# Enclosure_100x68_AMux-M.net
KiCad netlist of a schematic drawn in EAGLE
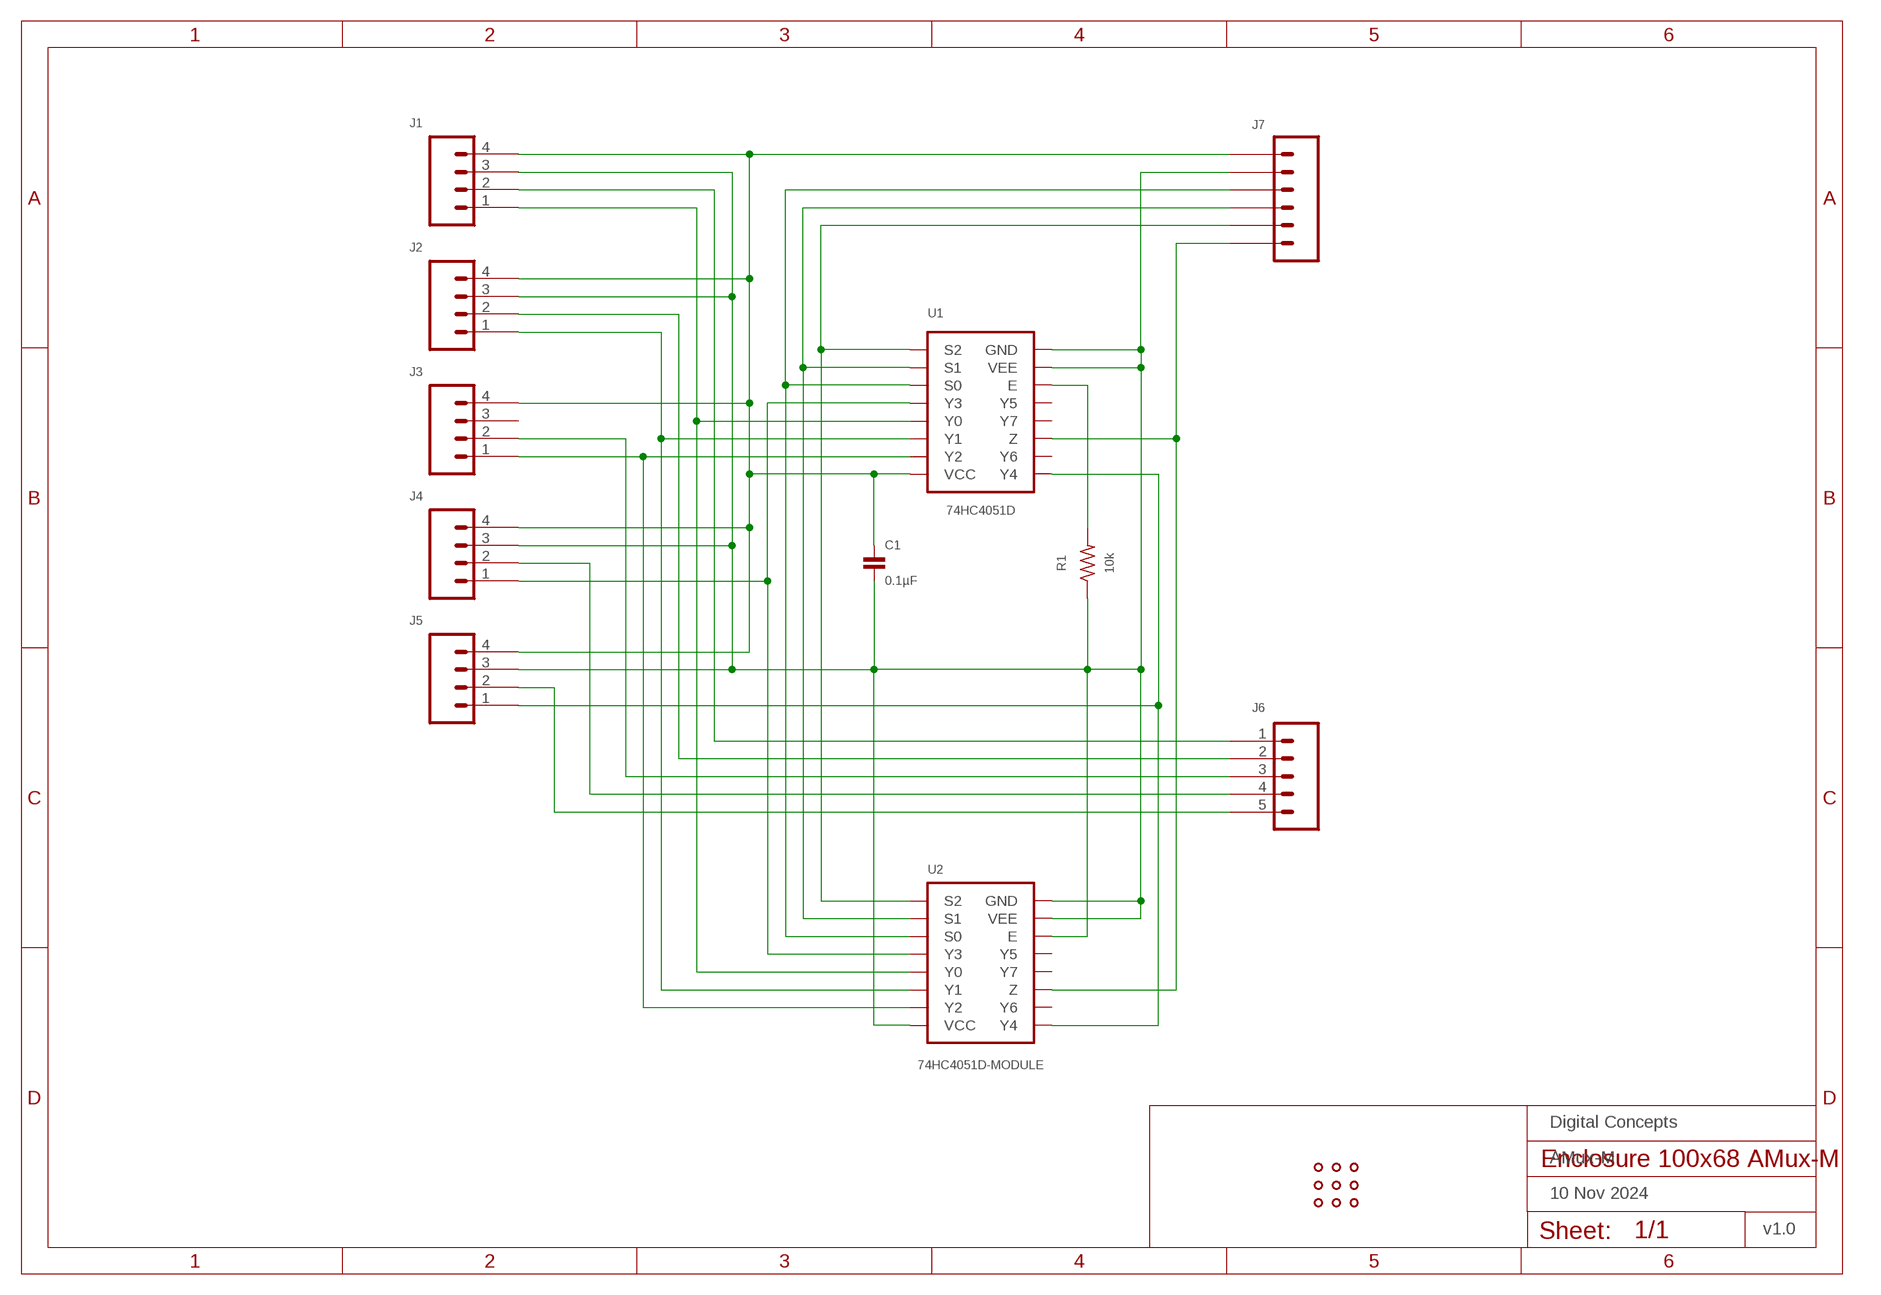
[diagram p0: schematic, sheet 1]

(export (version "E")
  (design (tool "Eeschema 10.0.6"))
  (components
    (comp (ref "C1")
      (value "0.1µF")
      (footprint "eagle-import:C0805")
      (libsource (lib "eagle-import") (part "CAPACITOR-0805"))
    )
    (comp (ref "J1")
      (value "HEADER-1X4-GENERIC")
      (footprint "eagle-import:CONN_04-GENERIC")
      (libsource (lib "eagle-import") (part "HEADER-1X4-GENERIC"))
    )
    (comp (ref "J2")
      (value "HEADER-1X4-GENERIC")
      (footprint "eagle-import:CONN_04-GENERIC")
      (libsource (lib "eagle-import") (part "HEADER-1X4-GENERIC"))
    )
    (comp (ref "J3")
      (value "HEADER-1X4-GENERIC")
      (footprint "eagle-import:CONN_04-GENERIC")
      (libsource (lib "eagle-import") (part "HEADER-1X4-GENERIC"))
    )
    (comp (ref "J4")
      (value "HEADER-1X4-GENERIC")
      (footprint "eagle-import:CONN_04-GENERIC")
      (libsource (lib "eagle-import") (part "HEADER-1X4-GENERIC"))
    )
    (comp (ref "J5")
      (value "HEADER-1X4-GENERIC")
      (footprint "eagle-import:CONN_04-GENERIC")
      (libsource (lib "eagle-import") (part "HEADER-1X4-GENERIC"))
    )
    (comp (ref "J6")
      (value "JST-PH2.0-5-HORIZONTAL")
      (footprint "eagle-import:JST-PH2.0-5-HORIZONTAL")
      (libsource (lib "eagle-import") (part "JST-PH2.0-5-HORIZONTAL"))
    )
    (comp (ref "J7")
      (value "JST-PH2.0-6-HORIZONTAL")
      (footprint "eagle-import:JST-PH2.0-6-HORIZONTAL")
      (libsource (lib "eagle-import") (part "JST-PH2.0-6-HORIZONTAL"))
    )
    (comp (ref "R1")
      (value "10k")
      (footprint "eagle-import:R0805")
      (libsource (lib "eagle-import") (part "RESISTORR0805"))
    )
    (comp (ref "U$1")
      (value "PROTO-34X22-AMUX")
      (footprint "eagle-import:PROTO-34X22-AMUX")
      (libsource (lib "eagle-import") (part "PROTO-34X22-AMUX"))
    )
    (comp (ref "U1")
      (value "74HC4051D")
      (footprint "eagle-import:SOP16")
      (libsource (lib "eagle-import") (part "74HC4051D"))
    )
    (comp (ref "U2")
      (value "74HC4051D-MODULE")
      (footprint "eagle-import:74HC4051D-MODULE")
      (libsource (lib "eagle-import") (part "74HC4051D-MODULE"))
    )
  )
  (nets
    (net (code "1") (name "Net-(J1-Pad2)") (class "Default")
      (node (ref "J1") (pin "2") (pinfunction "2_2") (pintype "passive"))
      (node (ref "J6") (pin "1") (pinfunction "1_1") (pintype "passive"))
    )
    (net (code "2") (name "Net-(J2-Pad2)") (class "Default")
      (node (ref "J2") (pin "2") (pinfunction "2_2") (pintype "passive"))
      (node (ref "J6") (pin "2") (pinfunction "2_2") (pintype "passive"))
    )
    (net (code "3") (name "Net-(J3-Pad2)") (class "Default")
      (node (ref "J3") (pin "2") (pinfunction "2_2") (pintype "passive"))
      (node (ref "J6") (pin "3") (pinfunction "3_3") (pintype "passive"))
    )
    (net (code "4") (name "Net-(J4-Pad2)") (class "Default")
      (node (ref "J4") (pin "2") (pinfunction "2_2") (pintype "passive"))
      (node (ref "J6") (pin "4") (pinfunction "4_4") (pintype "passive"))
    )
    (net (code "5") (name "Net-(J5-Pad2)") (class "Default")
      (node (ref "J5") (pin "2") (pinfunction "2_2") (pintype "passive"))
      (node (ref "J6") (pin "5") (pinfunction "5_5") (pintype "passive"))
    )
    (net (code "6") (name "Net-(U1-E)") (class "Default")
      (node (ref "R1") (pin "2") (pinfunction "2_2") (pintype "passive"))
      (node (ref "U1") (pin "6") (pinfunction "E_6") (pintype "bidirectional"))
    )
    (net (code "7") (name "Net-(U1-GND)") (class "Default")
      (node (ref "C1") (pin "2") (pinfunction "2_2") (pintype "passive"))
      (node (ref "J1") (pin "3") (pinfunction "3_3") (pintype "passive"))
      (node (ref "J2") (pin "3") (pinfunction "3_3") (pintype "passive"))
      (node (ref "J4") (pin "3") (pinfunction "3_3") (pintype "passive"))
      (node (ref "J5") (pin "3") (pinfunction "3_3") (pintype "passive"))
      (node (ref "J7") (pin "2") (pinfunction "2_2") (pintype "passive"))
      (node (ref "R1") (pin "1") (pinfunction "1_1") (pintype "passive"))
      (node (ref "U1") (pin "7") (pinfunction "VEE_7") (pintype "bidirectional"))
      (node (ref "U1") (pin "8") (pinfunction "GND_8") (pintype "bidirectional"))
      (node (ref "U2") (pin "E") (pinfunction "E_E") (pintype "bidirectional"))
      (node (ref "U2") (pin "GND@L") (pinfunction "GND_GND@L") (pintype "bidirectional"))
      (node (ref "U2") (pin "GND@R") (pinfunction "GND_GND@R") (pintype "bidirectional"))
      (node (ref "U2") (pin "VCC@L") (pinfunction "VCC_VCC@L") (pintype "bidirectional"))
      (node (ref "U2") (pin "VCC@R") (pinfunction "VCC_VCC@R") (pintype "bidirectional"))
      (node (ref "U2") (pin "VEE@L") (pinfunction "VEE_VEE@L") (pintype "bidirectional"))
      (node (ref "U2") (pin "VEE@R") (pinfunction "VEE_VEE@R") (pintype "bidirectional"))
    )
    (net (code "8") (name "Net-(U1-S0)") (class "Default")
      (node (ref "J7") (pin "3") (pinfunction "3_3") (pintype "passive"))
      (node (ref "U1") (pin "11") (pinfunction "S0_11") (pintype "bidirectional"))
      (node (ref "U2") (pin "S0") (pinfunction "S0_S0") (pintype "bidirectional"))
    )
    (net (code "9") (name "Net-(U1-S1)") (class "Default")
      (node (ref "J7") (pin "4") (pinfunction "4_4") (pintype "passive"))
      (node (ref "U1") (pin "10") (pinfunction "S1_10") (pintype "bidirectional"))
      (node (ref "U2") (pin "S1") (pinfunction "S1_S1") (pintype "bidirectional"))
    )
    (net (code "10") (name "Net-(U1-S2)") (class "Default")
      (node (ref "J7") (pin "5") (pinfunction "5_5") (pintype "passive"))
      (node (ref "U1") (pin "9") (pinfunction "S2_9") (pintype "bidirectional"))
      (node (ref "U2") (pin "S2") (pinfunction "S2_S2") (pintype "bidirectional"))
    )
    (net (code "11") (name "Net-(U1-VCC)") (class "Default")
      (node (ref "C1") (pin "1") (pinfunction "1_1") (pintype "passive"))
      (node (ref "J1") (pin "4") (pinfunction "4_4") (pintype "passive"))
      (node (ref "J2") (pin "4") (pinfunction "4_4") (pintype "passive"))
      (node (ref "J3") (pin "4") (pinfunction "4_4") (pintype "passive"))
      (node (ref "J4") (pin "4") (pinfunction "4_4") (pintype "passive"))
      (node (ref "J5") (pin "4") (pinfunction "4_4") (pintype "passive"))
      (node (ref "J7") (pin "1") (pinfunction "1_1") (pintype "passive"))
      (node (ref "U1") (pin "16") (pinfunction "VCC_16") (pintype "bidirectional"))
    )
    (net (code "12") (name "Net-(U1-Y0)") (class "Default")
      (node (ref "J1") (pin "1") (pinfunction "1_1") (pintype "passive"))
      (node (ref "U1") (pin "13") (pinfunction "Y0_13") (pintype "bidirectional"))
      (node (ref "U2") (pin "Y0") (pinfunction "Y0_Y0") (pintype "bidirectional"))
    )
    (net (code "13") (name "Net-(U1-Y1)") (class "Default")
      (node (ref "J2") (pin "1") (pinfunction "1_1") (pintype "passive"))
      (node (ref "U1") (pin "14") (pinfunction "Y1_14") (pintype "bidirectional"))
      (node (ref "U2") (pin "Y1") (pinfunction "Y1_Y1") (pintype "bidirectional"))
    )
    (net (code "14") (name "Net-(U1-Y2)") (class "Default")
      (node (ref "J3") (pin "1") (pinfunction "1_1") (pintype "passive"))
      (node (ref "U1") (pin "15") (pinfunction "Y2_15") (pintype "bidirectional"))
      (node (ref "U2") (pin "Y2") (pinfunction "Y2_Y2") (pintype "bidirectional"))
    )
    (net (code "15") (name "Net-(U1-Y3)") (class "Default")
      (node (ref "J4") (pin "1") (pinfunction "1_1") (pintype "passive"))
      (node (ref "U1") (pin "12") (pinfunction "Y3_12") (pintype "bidirectional"))
      (node (ref "U2") (pin "Y3") (pinfunction "Y3_Y3") (pintype "bidirectional"))
    )
    (net (code "16") (name "Net-(U1-Y4)") (class "Default")
      (node (ref "J5") (pin "1") (pinfunction "1_1") (pintype "passive"))
      (node (ref "U1") (pin "1") (pinfunction "Y4_1") (pintype "bidirectional"))
      (node (ref "U2") (pin "Y4") (pinfunction "Y4_Y4") (pintype "bidirectional"))
    )
    (net (code "17") (name "Net-(U1-Z)") (class "Default")
      (node (ref "J7") (pin "6") (pinfunction "6_6") (pintype "passive"))
      (node (ref "U1") (pin "3") (pinfunction "Z_3") (pintype "bidirectional"))
      (node (ref "U2") (pin "Z") (pinfunction "Z_Z") (pintype "bidirectional"))
    )
    (net (code "18") (name "unconnected-(J3-Pad3)") (class "Default")
      (node (ref "J3") (pin "3") (pinfunction "3_3") (pintype "passive"))
    )
    (net (code "19") (name "unconnected-(U1-Y5-Pad5)") (class "Default")
      (node (ref "U1") (pin "5") (pinfunction "Y5_5") (pintype "bidirectional"))
    )
    (net (code "20") (name "unconnected-(U1-Y6-Pad2)") (class "Default")
      (node (ref "U1") (pin "2") (pinfunction "Y6_2") (pintype "bidirectional"))
    )
    (net (code "21") (name "unconnected-(U1-Y7-Pad4)") (class "Default")
      (node (ref "U1") (pin "4") (pinfunction "Y7_4") (pintype "bidirectional"))
    )
    (net (code "22") (name "unconnected-(U2-PadY5)") (class "Default")
      (node (ref "U2") (pin "Y5") (pinfunction "Y5_Y5") (pintype "bidirectional"))
    )
    (net (code "23") (name "unconnected-(U2-PadY6)") (class "Default")
      (node (ref "U2") (pin "Y6") (pinfunction "Y6_Y6") (pintype "bidirectional"))
    )
    (net (code "24") (name "unconnected-(U2-PadY7)") (class "Default")
      (node (ref "U2") (pin "Y7") (pinfunction "Y7_Y7") (pintype "bidirectional"))
    )
  )
)
